# ArduinoUnoQ.net
KiCad netlist of a schematic drawn in Altium Designer
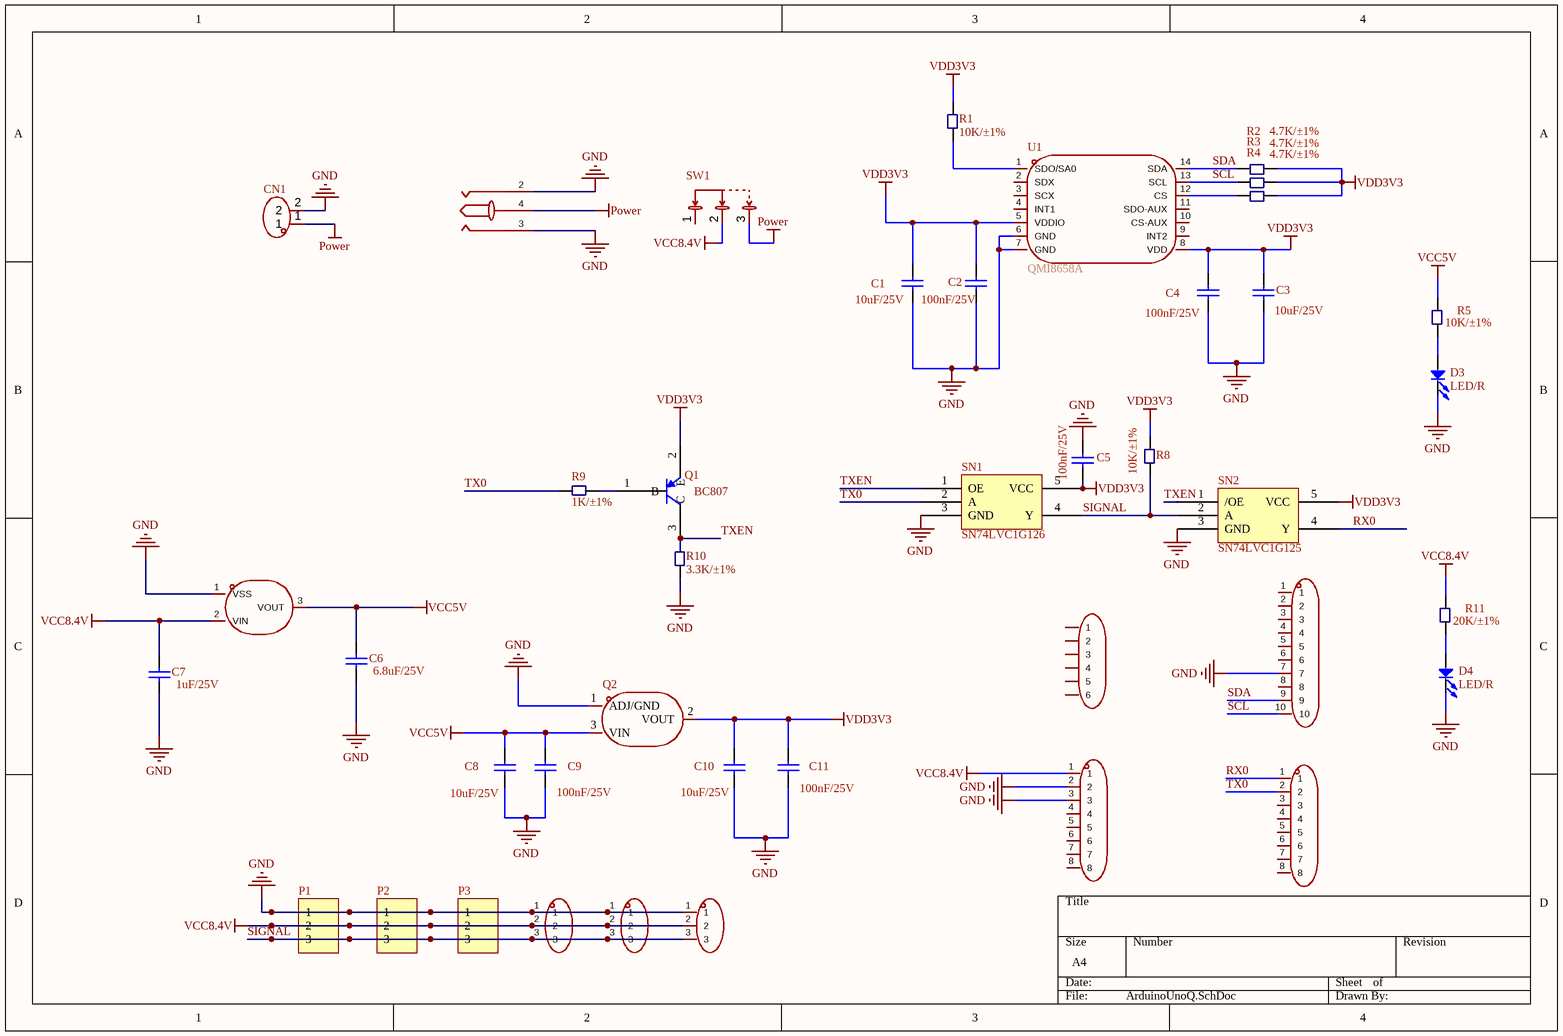
[diagram p0: ArduinoUnoQ.SchDoc]

(export (version "E")
  (design (tool "Eeschema 10.0.6"))
  (components
    (comp (ref "C1")
      (value "10uF/25V")
      (footprint "C0603")
      (description "0603贴片电容，±10%，50V")
      (fields (field (name "PUBLISHER") "Altium Limited"))
      (libsource (lib "ArduinoUnoQ") (part "0603 C"))
    )
    (comp (ref "C2")
      (value "100nF/25V")
      (footprint "C0603")
      (description "0603贴片电容，±10%，50V")
      (fields (field (name "PUBLISHER") "Altium Limited"))
      (libsource (lib "ArduinoUnoQ") (part "0603 C"))
    )
    (comp (ref "C3")
      (value "10uF/25V")
      (footprint "C0603")
      (description "0603贴片电容，±10%，50V")
      (fields (field (name "PUBLISHER") "Altium Limited"))
      (libsource (lib "ArduinoUnoQ") (part "0603 C"))
    )
    (comp (ref "C4")
      (value "100nF/25V")
      (footprint "C0603")
      (description "0603贴片电容，±10%，50V")
      (fields (field (name "PUBLISHER") "Altium Limited"))
      (libsource (lib "ArduinoUnoQ") (part "0603 C"))
    )
    (comp (ref "C5")
      (value "100nF/25V")
      (footprint "C0603")
      (description "贴片电容")
      (libsource (lib "Cap") (part "0603 10nF (103) 10% 50V"))
    )
    (comp (ref "C6")
      (value "6.8uF/25V")
      (footprint "C0603")
      (description "0603贴片电容，±10%，50V")
      (fields (field (name "PUBLISHER") "Altium Limited"))
      (libsource (lib "ArduinoUnoQ") (part "0603 C"))
    )
    (comp (ref "C7")
      (value "1uF/25V")
      (footprint "C0603")
      (description "0603贴片电容，±10%，50V")
      (fields (field (name "PUBLISHER") "Altium Limited"))
      (libsource (lib "ArduinoUnoQ") (part "0603 C"))
    )
    (comp (ref "C8")
      (value "10uF/25V")
      (footprint "C0603")
      (description "0603贴片电容，±10%，50V")
      (fields (field (name "PUBLISHER") "Altium Limited"))
      (libsource (lib "ArduinoUnoQ") (part "0603 C"))
    )
    (comp (ref "C9")
      (value "100nF/25V")
      (footprint "C0603")
      (description "0603贴片电容，±10%，50V")
      (fields (field (name "PUBLISHER") "Altium Limited"))
      (libsource (lib "ArduinoUnoQ") (part "0603 C"))
    )
    (comp (ref "C10")
      (value "10uF/25V")
      (footprint "C0603")
      (description "0603贴片电容，±10%，50V")
      (fields (field (name "PUBLISHER") "Altium Limited"))
      (libsource (lib "ArduinoUnoQ") (part "0603 C"))
    )
    (comp (ref "C11")
      (value "100nF/25V")
      (footprint "C0603")
      (description "0603贴片电容，±10%，50V")
      (fields (field (name "PUBLISHER") "Altium Limited"))
      (libsource (lib "ArduinoUnoQ") (part "0603 C"))
    )
    (comp (ref "CN1")
      (value "ZX-XH2.54-2PWZ")
      (footprint "CONN-TH_2P-P2.50_ZX-XH2.54-2PWZ")
      (fields (field (name "MANUFACTURER") "Megastar(兆星)"))
      (libsource (lib "ArduinoUnoQ") (part "ZX-XH2.54-2PWZ"))
    )
    (comp (ref "D3")
      (value "LED/R")
      (footprint "D_SOD_523")
      (description "Typical INFRARED GaAs LED")
      (fields (field (name "PUBLISHER") "Altium Limited"))
      (libsource (lib "luwu") (part "LED"))
    )
    (comp (ref "D4")
      (value "LED/R")
      (footprint "D_SOD_523")
      (description "Typical INFRARED GaAs LED")
      (fields (field (name "PUBLISHER") "Altium Limited"))
      (libsource (lib "luwu") (part "LED"))
    )
    (comp (ref "DC1")
      (value "kh-dc-007b-2.1g")
      (footprint "DC-IN-TH_KH-DC-007B-2.1G")
      (description "连接器类型:DC电源插座;安装方式:弯插;触点内径:-;触点外径:-;额定电流:3A;额定电压:50V;工作温度:-30℃~+70℃;")
      (fields
        (field (name "MANUFACTURER") "kinghelm(金航标)")
        (field (name "MANUFACTURERPART") "KH-DC-007B-2.1G")
      )
      (libsource (lib "ArduinoUnoQ") (part "kh-dc-007b-2.1g"))
    )
    (comp (ref "H1")
      (value "pz254v-11-06p")
      (footprint "HDR-TH_6P-P2.54-V-M-1")
      (fields (field (name "MANUFACTURER") "BOOMELE(博穆精密)") (field (name "MANUFACTURERPART") "2.54-1x6P直针"))
      (libsource (lib "ArduinoUnoQ") (part "pz254v-11-06p"))
    )
    (comp (ref "H2")
      (value "pz254v-11-10p")
      (footprint "HDR-TH_10P-P2.54-V-M")
      (fields (field (name "MANUFACTURER") "XFCN(兴飞)") (field (name "MANUFACTURERPART") "PZ254V-11-10P"))
      (libsource (lib "ArduinoUnoQ") (part "pz254v-11-10p"))
    )
    (comp (ref "H3")
      (value "pz254v-11-08p")
      (footprint "HDR-TH_8P-P2.54-V-M")
      (fields (field (name "MANUFACTURER") "XFCN(兴飞)") (field (name "MANUFACTURERPART") "PZ254V-11-08P"))
      (libsource (lib "ArduinoUnoQ") (part "pz254v-11-08p"))
    )
    (comp (ref "H4")
      (value "pz254v-11-08p")
      (footprint "HDR-TH_8P-P2.54-V-M")
      (fields (field (name "MANUFACTURER") "XFCN(兴飞)") (field (name "MANUFACTURERPART") "PZ254V-11-08P"))
      (libsource (lib "ArduinoUnoQ") (part "pz254v-11-08p"))
    )
    (comp (ref "P1")
      (value "Header 3")
      (footprint "MX 1.25-WI-3P")
      (description "Header, 3-Pin")
      (fields (field (name "PUBLISHER") "Altium Limited"))
      (libsource (lib "Miscellaneous Connectors") (part "Header 3"))
    )
    (comp (ref "P2")
      (value "Header 3")
      (footprint "MX 1.25-WI-3P")
      (description "Header, 3-Pin")
      (fields (field (name "PUBLISHER") "Altium Limited"))
      (libsource (lib "Miscellaneous Connectors") (part "Header 3"))
    )
    (comp (ref "P3")
      (value "Header 3")
      (footprint "MX 1.25-WI-3P")
      (description "Header, 3-Pin")
      (fields (field (name "PUBLISHER") "Altium Limited"))
      (libsource (lib "Miscellaneous Connectors") (part "Header 3"))
    )
    (comp (ref "Q1")
      (value "BC807")
      (footprint "SOT-23-3")
      (description "三极管BJT")
      (fields (field (name "PUBLISHER") "Altium Limited"))
      (libsource (lib "XGOMINI_V2") (part "PNP 60V 600mA"))
    )
    (comp (ref "Q2")
      (value "AMS1117-3.3V")
      (footprint "SOT-89-3_L4.5-W2.5-P1.50-LS4.2-BR")
      (description "输入18V 输出3.3V 1A，SOT-89封装")
      (fields (field (name "MANUFACTURER") "MSKSEMI(美森科)"))
      (libsource (lib "ArduinoUnoQ") (part "AMS1117-3.3V_SOT89"))
    )
    (comp (ref "R1")
      (value "10K/±1%")
      (footprint "R0603")
      (description "Resistor")
      (fields (field (name "PUBLISHER") "Altium Limited"))
      (libsource (lib "RM-maincontrol-2019 2.0") (part "Res2_1"))
    )
    (comp (ref "R2")
      (value "4.7K/±1%")
      (footprint "R0603")
      (description "Resistor")
      (fields (field (name "PUBLISHER") "Altium Limited"))
      (libsource (lib "RM-maincontrol-2019 2.0") (part "Res2_1"))
    )
    (comp (ref "R3")
      (value "4.7K/±1%")
      (footprint "R0603")
      (description "Resistor")
      (fields (field (name "PUBLISHER") "Altium Limited"))
      (libsource (lib "RM-maincontrol-2019 2.0") (part "Res2_1"))
    )
    (comp (ref "R4")
      (value "4.7K/±1%")
      (footprint "R0603")
      (description "Resistor")
      (fields (field (name "PUBLISHER") "Altium Limited"))
      (libsource (lib "RM-maincontrol-2019 2.0") (part "Res2_1"))
    )
    (comp (ref "R5")
      (value "10K/±1%")
      (footprint "R0603")
      (description "Resistor")
      (fields (field (name "PUBLISHER") "Altium Limited"))
      (libsource (lib "RM-maincontrol-2019 2.0") (part "Res2_1"))
    )
    (comp (ref "R8")
      (value "10K/±1%")
      (footprint "R0603")
      (description "Resistor")
      (fields (field (name "PUBLISHER") "Altium Limited"))
      (libsource (lib "RM-maincontrol-2019 2.0") (part "Res2_1"))
    )
    (comp (ref "R9")
      (value "1K/±1%")
      (footprint "R0603")
      (description "Resistor")
      (fields (field (name "PUBLISHER") "Altium Limited"))
      (libsource (lib "RM-maincontrol-2019 2.0") (part "Res2_1"))
    )
    (comp (ref "R10")
      (value "3.3K/±1%")
      (footprint "R0603")
      (description "Resistor")
      (fields (field (name "PUBLISHER") "Altium Limited"))
      (libsource (lib "RM-maincontrol-2019 2.0") (part "Res2_1"))
    )
    (comp (ref "R11")
      (value "20K/±1%")
      (footprint "R0603")
      (description "Resistor")
      (fields (field (name "PUBLISHER") "Altium Limited"))
      (libsource (lib "RM-maincontrol-2019 2.0") (part "Res2_1"))
    )
    (comp (ref "SN1")
      (value "SN74LVC1G126")
      (footprint "SOT_23_5")
      (description "输出缓冲器")
      (libsource (lib "XGOLITE_V2") (part "SN74LVC1G126"))
    )
    (comp (ref "SN2")
      (value "SN74LVC1G125")
      (footprint "SOT_23_5")
      (libsource (lib "XDOG") (part "SN74LVC1G125"))
    )
    (comp (ref "SW1")
      (value "SS-12D06L5")
      (footprint "SW-TH_3P-P4.70_L11.1-W12.7")
      (description "电路结构:单刀双掷;安装方式:-;开关颜色:黑色;额定电流:3A;额定电压:125V;工作寿命:1万次;")
      (fields (field (name "MANUFACTURER") "XKB Connection(中国星坤)"))
      (libsource (lib "ArduinoUnoQ") (part "SS-12D06L5"))
    )
    (comp (ref "U1")
      (value "QMI8658A")
      (footprint "LGA-14_L3.0-W2.5-P0.50-TL")
      (description "六轴陀螺仪  陀螺仪量程(MAX) ±2048dps  加速度计量程(MAX) ±16g")
      (libsource (lib "ArduinoUnoQ") (part "QMI8658A"))
    )
    (comp (ref "U2")
      (value "h7651-50pr")
      (footprint "SOT-89-3_L4.5-W2.5-P1.50-LS4.2-BR")
      (description "输出极性:正极;工作电压:8.5V;输出电压:5V;输出电流:1A;电源纹波抑制比(PSRR):-;输出类型:固定;")
      (fields (field (name "MANUFACTURER") "Siproin(上海矽朋)") (field (name "MANUFACTURERPART") "H7651-50PR"))
      (libsource (lib "ArduinoUnoQ") (part "h7651-50pr"))
    )
    (comp (ref "U3")
      (value "292253-3")
      (footprint "CONN-TH_3P-P2.00_TE_292253-3")
      (description "插针结构:1x3P;间距:2mm;安装方式:弯插;总PIN数:3P;排数:1;每排PIN数:3;额定电流:4A;触头材质:黄铜;触头镀层:锡;工作温度:-40℃~+105℃;")
      (fields (field (name "MANUFACTURER") "TE Connectivity(泰科电子)"))
      (libsource (lib "ArduinoUnoQ") (part "292253-3"))
    )
    (comp (ref "U4")
      (value "292253-3")
      (footprint "CONN-TH_3P-P2.00_TE_292253-3")
      (description "插针结构:1x3P;间距:2mm;安装方式:弯插;总PIN数:3P;排数:1;每排PIN数:3;额定电流:4A;触头材质:黄铜;触头镀层:锡;工作温度:-40℃~+105℃;")
      (fields (field (name "MANUFACTURER") "TE Connectivity(泰科电子)"))
      (libsource (lib "ArduinoUnoQ") (part "292253-3"))
    )
    (comp (ref "U5")
      (value "292253-3")
      (footprint "CONN-TH_3P-P2.00_TE_292253-3")
      (description "插针结构:1x3P;间距:2mm;安装方式:弯插;总PIN数:3P;排数:1;每排PIN数:3;额定电流:4A;触头材质:黄铜;触头镀层:锡;工作温度:-40℃~+105℃;")
      (fields (field (name "MANUFACTURER") "TE Connectivity(泰科电子)"))
      (libsource (lib "ArduinoUnoQ") (part "292253-3"))
    )
  )
  (nets
    (net (code "1") (name "/RX0") (class "Default")
      (node (ref "H4") (pin "1") (pinfunction "1_1") (pintype "passive"))
      (node (ref "SN2") (pin "4") (pinfunction "Y_4") (pintype "passive"))
    )
    (net (code "2") (name "/SCL") (class "Default")
      (node (ref "H2") (pin "10") (pinfunction "10_10") (pintype "passive"))
      (node (ref "R3") (pin "1") (pinfunction "1_1") (pintype "passive"))
      (node (ref "U1") (pin "13") (pinfunction "SCL_13") (pintype "passive"))
    )
    (net (code "3") (name "/SDA") (class "Default")
      (node (ref "H2") (pin "9") (pinfunction "9_9") (pintype "passive"))
      (node (ref "R2") (pin "1") (pinfunction "1_1") (pintype "passive"))
      (node (ref "U1") (pin "14") (pinfunction "SDA_14") (pintype "passive"))
    )
    (net (code "4") (name "/SIGNAL") (class "Default")
      (node (ref "P1") (pin "3") (pinfunction "3_3") (pintype "passive"))
      (node (ref "P2") (pin "3") (pinfunction "3_3") (pintype "passive"))
      (node (ref "P3") (pin "3") (pinfunction "3_3") (pintype "passive"))
      (node (ref "R8") (pin "2") (pinfunction "2_2") (pintype "passive"))
      (node (ref "SN1") (pin "4") (pinfunction "Y_4") (pintype "passive"))
      (node (ref "SN2") (pin "2") (pinfunction "A_2") (pintype "passive"))
      (node (ref "U3") (pin "3") (pinfunction "3_3") (pintype "passive"))
      (node (ref "U4") (pin "3") (pinfunction "3_3") (pintype "passive"))
      (node (ref "U5") (pin "3") (pinfunction "3_3") (pintype "passive"))
    )
    (net (code "5") (name "/TX0") (class "Default")
      (node (ref "H4") (pin "2") (pinfunction "2_2") (pintype "passive"))
      (node (ref "R9") (pin "2") (pinfunction "2_2") (pintype "passive"))
      (node (ref "SN1") (pin "2") (pinfunction "A_2") (pintype "passive"))
    )
    (net (code "6") (name "/TXEN") (class "Default")
      (node (ref "Q1") (pin "3") (pinfunction "C_3") (pintype "passive"))
      (node (ref "R10") (pin "1") (pinfunction "1_1") (pintype "passive"))
      (node (ref "SN1") (pin "1") (pinfunction "OE_1") (pintype "passive"))
      (node (ref "SN2") (pin "1") (pinfunction "/OE_1") (pintype "passive"))
    )
    (net (code "7") (name "GND") (class "Default")
      (node (ref "C1") (pin "1") (pinfunction "1_1") (pintype "passive"))
      (node (ref "C10") (pin "1") (pinfunction "1_1") (pintype "passive"))
      (node (ref "C11") (pin "1") (pinfunction "1_1") (pintype "passive"))
      (node (ref "C2") (pin "1") (pinfunction "1_1") (pintype "passive"))
      (node (ref "C3") (pin "1") (pinfunction "1_1") (pintype "passive"))
      (node (ref "C4") (pin "1") (pinfunction "1_1") (pintype "passive"))
      (node (ref "C5") (pin "2") (pinfunction "2_2") (pintype "passive"))
      (node (ref "C6") (pin "1") (pinfunction "1_1") (pintype "passive"))
      (node (ref "C7") (pin "1") (pinfunction "1_1") (pintype "passive"))
      (node (ref "C8") (pin "1") (pinfunction "1_1") (pintype "passive"))
      (node (ref "C9") (pin "1") (pinfunction "1_1") (pintype "passive"))
      (node (ref "CN1") (pin "2") (pinfunction "2_2") (pintype "passive"))
      (node (ref "D3") (pin "2") (pinfunction "K_2") (pintype "passive"))
      (node (ref "D4") (pin "2") (pinfunction "K_2") (pintype "passive"))
      (node (ref "DC1") (pin "2") (pinfunction "2_2") (pintype "passive"))
      (node (ref "DC1") (pin "3") (pinfunction "3_3") (pintype "passive"))
      (node (ref "H2") (pin "7") (pinfunction "7_7") (pintype "passive"))
      (node (ref "H3") (pin "2") (pinfunction "2_2") (pintype "passive"))
      (node (ref "H3") (pin "3") (pinfunction "3_3") (pintype "passive"))
      (node (ref "P1") (pin "1") (pinfunction "1_1") (pintype "passive"))
      (node (ref "P2") (pin "1") (pinfunction "1_1") (pintype "passive"))
      (node (ref "P3") (pin "1") (pinfunction "1_1") (pintype "passive"))
      (node (ref "Q2") (pin "1") (pinfunction "ADJ/GND_1") (pintype "passive"))
      (node (ref "R10") (pin "2") (pinfunction "2_2") (pintype "passive"))
      (node (ref "SN1") (pin "3") (pinfunction "GND_3") (pintype "passive"))
      (node (ref "SN2") (pin "3") (pinfunction "GND_3") (pintype "passive"))
      (node (ref "U1") (pin "6") (pinfunction "GND_6") (pintype "passive"))
      (node (ref "U1") (pin "7") (pinfunction "GND_7") (pintype "passive"))
      (node (ref "U2") (pin "1") (pinfunction "VSS_1") (pintype "passive"))
      (node (ref "U3") (pin "1") (pinfunction "1_1") (pintype "passive"))
      (node (ref "U4") (pin "1") (pinfunction "1_1") (pintype "passive"))
      (node (ref "U5") (pin "1") (pinfunction "1_1") (pintype "passive"))
    )
    (net (code "8") (name "Net-(D3-A)") (class "Default")
      (node (ref "D3") (pin "1") (pinfunction "A_1") (pintype "passive"))
      (node (ref "R5") (pin "2") (pinfunction "2_2") (pintype "passive"))
    )
    (net (code "9") (name "Net-(D4-A)") (class "Default")
      (node (ref "D4") (pin "1") (pinfunction "A_1") (pintype "passive"))
      (node (ref "R11") (pin "2") (pinfunction "2_2") (pintype "passive"))
    )
    (net (code "10") (name "Net-(Q1-B)") (class "Default")
      (node (ref "Q1") (pin "1") (pinfunction "B_1") (pintype "passive"))
      (node (ref "R9") (pin "1") (pinfunction "1_1") (pintype "passive"))
    )
    (net (code "11") (name "Net-(U1-CS)") (class "Default")
      (node (ref "R4") (pin "1") (pinfunction "1_1") (pintype "passive"))
      (node (ref "U1") (pin "12") (pinfunction "CS_12") (pintype "passive"))
    )
    (net (code "12") (name "Net-(U1-SDO{slash}SA0)") (class "Default")
      (node (ref "R1") (pin "2") (pinfunction "2_2") (pintype "passive"))
      (node (ref "U1") (pin "1") (pinfunction "SDO/SA0_1") (pintype "passive"))
    )
    (net (code "13") (name "Power") (class "Default")
      (node (ref "CN1") (pin "1") (pinfunction "1_1") (pintype "passive"))
      (node (ref "DC1") (pin "4") (pinfunction "4_4") (pintype "passive"))
      (node (ref "SW1") (pin "3") (pinfunction "3_3") (pintype "passive"))
    )
    (net (code "14") (name "VCC5V") (class "Default")
      (node (ref "C6") (pin "2") (pinfunction "2_2") (pintype "passive"))
      (node (ref "C8") (pin "2") (pinfunction "2_2") (pintype "passive"))
      (node (ref "C9") (pin "2") (pinfunction "2_2") (pintype "passive"))
      (node (ref "Q2") (pin "3") (pinfunction "VIN_3") (pintype "passive"))
      (node (ref "R5") (pin "1") (pinfunction "1_1") (pintype "passive"))
      (node (ref "U2") (pin "3") (pinfunction "VOUT_3") (pintype "passive"))
    )
    (net (code "15") (name "VCC8.4V") (class "Default")
      (node (ref "C7") (pin "2") (pinfunction "2_2") (pintype "passive"))
      (node (ref "H3") (pin "1") (pinfunction "1_1") (pintype "passive"))
      (node (ref "P1") (pin "2") (pinfunction "2_2") (pintype "passive"))
      (node (ref "P2") (pin "2") (pinfunction "2_2") (pintype "passive"))
      (node (ref "P3") (pin "2") (pinfunction "2_2") (pintype "passive"))
      (node (ref "R11") (pin "1") (pinfunction "1_1") (pintype "passive"))
      (node (ref "SW1") (pin "2") (pinfunction "2_2") (pintype "passive"))
      (node (ref "U2") (pin "2") (pinfunction "VIN_2") (pintype "passive"))
      (node (ref "U3") (pin "2") (pinfunction "2_2") (pintype "passive"))
      (node (ref "U4") (pin "2") (pinfunction "2_2") (pintype "passive"))
      (node (ref "U5") (pin "2") (pinfunction "2_2") (pintype "passive"))
    )
    (net (code "16") (name "VDD3V3") (class "Default")
      (node (ref "C1") (pin "2") (pinfunction "2_2") (pintype "passive"))
      (node (ref "C10") (pin "2") (pinfunction "2_2") (pintype "passive"))
      (node (ref "C11") (pin "2") (pinfunction "2_2") (pintype "passive"))
      (node (ref "C2") (pin "2") (pinfunction "2_2") (pintype "passive"))
      (node (ref "C3") (pin "2") (pinfunction "2_2") (pintype "passive"))
      (node (ref "C4") (pin "2") (pinfunction "2_2") (pintype "passive"))
      (node (ref "C5") (pin "1") (pinfunction "1_1") (pintype "passive"))
      (node (ref "Q1") (pin "2") (pinfunction "E_2") (pintype "passive"))
      (node (ref "Q2") (pin "2") (pinfunction "VOUT_2") (pintype "passive"))
      (node (ref "R1") (pin "1") (pinfunction "1_1") (pintype "passive"))
      (node (ref "R2") (pin "2") (pinfunction "2_2") (pintype "passive"))
      (node (ref "R3") (pin "2") (pinfunction "2_2") (pintype "passive"))
      (node (ref "R4") (pin "2") (pinfunction "2_2") (pintype "passive"))
      (node (ref "R8") (pin "1") (pinfunction "1_1") (pintype "passive"))
      (node (ref "SN1") (pin "5") (pinfunction "VCC_5") (pintype "passive"))
      (node (ref "SN2") (pin "5") (pinfunction "VCC_5") (pintype "passive"))
      (node (ref "U1") (pin "5") (pinfunction "VDDIO_5") (pintype "passive"))
      (node (ref "U1") (pin "8") (pinfunction "VDD_8") (pintype "passive"))
    )
    (net (code "17") (name "unconnected-(H1-Pad1)") (class "Default")
      (node (ref "H1") (pin "1") (pinfunction "1_1") (pintype "passive"))
    )
    (net (code "18") (name "unconnected-(H1-Pad2)") (class "Default")
      (node (ref "H1") (pin "2") (pinfunction "2_2") (pintype "passive"))
    )
    (net (code "19") (name "unconnected-(H1-Pad3)") (class "Default")
      (node (ref "H1") (pin "3") (pinfunction "3_3") (pintype "passive"))
    )
    (net (code "20") (name "unconnected-(H1-Pad4)") (class "Default")
      (node (ref "H1") (pin "4") (pinfunction "4_4") (pintype "passive"))
    )
    (net (code "21") (name "unconnected-(H1-Pad5)") (class "Default")
      (node (ref "H1") (pin "5") (pinfunction "5_5") (pintype "passive"))
    )
    (net (code "22") (name "unconnected-(H1-Pad6)") (class "Default")
      (node (ref "H1") (pin "6") (pinfunction "6_6") (pintype "passive"))
    )
    (net (code "23") (name "unconnected-(H2-Pad1)") (class "Default")
      (node (ref "H2") (pin "1") (pinfunction "1_1") (pintype "passive"))
    )
    (net (code "24") (name "unconnected-(H2-Pad2)") (class "Default")
      (node (ref "H2") (pin "2") (pinfunction "2_2") (pintype "passive"))
    )
    (net (code "25") (name "unconnected-(H2-Pad3)") (class "Default")
      (node (ref "H2") (pin "3") (pinfunction "3_3") (pintype "passive"))
    )
    (net (code "26") (name "unconnected-(H2-Pad4)") (class "Default")
      (node (ref "H2") (pin "4") (pinfunction "4_4") (pintype "passive"))
    )
    (net (code "27") (name "unconnected-(H2-Pad5)") (class "Default")
      (node (ref "H2") (pin "5") (pinfunction "5_5") (pintype "passive"))
    )
    (net (code "28") (name "unconnected-(H2-Pad6)") (class "Default")
      (node (ref "H2") (pin "6") (pinfunction "6_6") (pintype "passive"))
    )
    (net (code "29") (name "unconnected-(H2-Pad8)") (class "Default")
      (node (ref "H2") (pin "8") (pinfunction "8_8") (pintype "passive"))
    )
    (net (code "30") (name "unconnected-(H3-Pad4)") (class "Default")
      (node (ref "H3") (pin "4") (pinfunction "4_4") (pintype "passive"))
    )
    (net (code "31") (name "unconnected-(H3-Pad5)") (class "Default")
      (node (ref "H3") (pin "5") (pinfunction "5_5") (pintype "passive"))
    )
    (net (code "32") (name "unconnected-(H3-Pad6)") (class "Default")
      (node (ref "H3") (pin "6") (pinfunction "6_6") (pintype "passive"))
    )
    (net (code "33") (name "unconnected-(H3-Pad7)") (class "Default")
      (node (ref "H3") (pin "7") (pinfunction "7_7") (pintype "passive"))
    )
    (net (code "34") (name "unconnected-(H3-Pad8)") (class "Default")
      (node (ref "H3") (pin "8") (pinfunction "8_8") (pintype "passive"))
    )
    (net (code "35") (name "unconnected-(H4-Pad3)") (class "Default")
      (node (ref "H4") (pin "3") (pinfunction "3_3") (pintype "passive"))
    )
    (net (code "36") (name "unconnected-(H4-Pad4)") (class "Default")
      (node (ref "H4") (pin "4") (pinfunction "4_4") (pintype "passive"))
    )
    (net (code "37") (name "unconnected-(H4-Pad5)") (class "Default")
      (node (ref "H4") (pin "5") (pinfunction "5_5") (pintype "passive"))
    )
    (net (code "38") (name "unconnected-(H4-Pad6)") (class "Default")
      (node (ref "H4") (pin "6") (pinfunction "6_6") (pintype "passive"))
    )
    (net (code "39") (name "unconnected-(H4-Pad7)") (class "Default")
      (node (ref "H4") (pin "7") (pinfunction "7_7") (pintype "passive"))
    )
    (net (code "40") (name "unconnected-(H4-Pad8)") (class "Default")
      (node (ref "H4") (pin "8") (pinfunction "8_8") (pintype "passive"))
    )
    (net (code "41") (name "unconnected-(SW1-Pad1)") (class "Default")
      (node (ref "SW1") (pin "1") (pinfunction "1_1") (pintype "passive"))
    )
    (net (code "42") (name "unconnected-(U1-CS-AUX-Pad10)") (class "Default")
      (node (ref "U1") (pin "10") (pinfunction "CS-AUX_10") (pintype "passive"))
    )
    (net (code "43") (name "unconnected-(U1-INT1-Pad4)") (class "Default")
      (node (ref "U1") (pin "4") (pinfunction "INT1_4") (pintype "passive"))
    )
    (net (code "44") (name "unconnected-(U1-INT2-Pad9)") (class "Default")
      (node (ref "U1") (pin "9") (pinfunction "INT2_9") (pintype "passive"))
    )
    (net (code "45") (name "unconnected-(U1-SCX-Pad3)") (class "Default")
      (node (ref "U1") (pin "3") (pinfunction "SCX_3") (pintype "passive"))
    )
    (net (code "46") (name "unconnected-(U1-SDO-AUX-Pad11)") (class "Default")
      (node (ref "U1") (pin "11") (pinfunction "SDO-AUX_11") (pintype "passive"))
    )
    (net (code "47") (name "unconnected-(U1-SDX-Pad2)") (class "Default")
      (node (ref "U1") (pin "2") (pinfunction "SDX_2") (pintype "passive"))
    )
  )
)
